# Main.net
KiCad netlist of a schematic drawn in Altium Designer
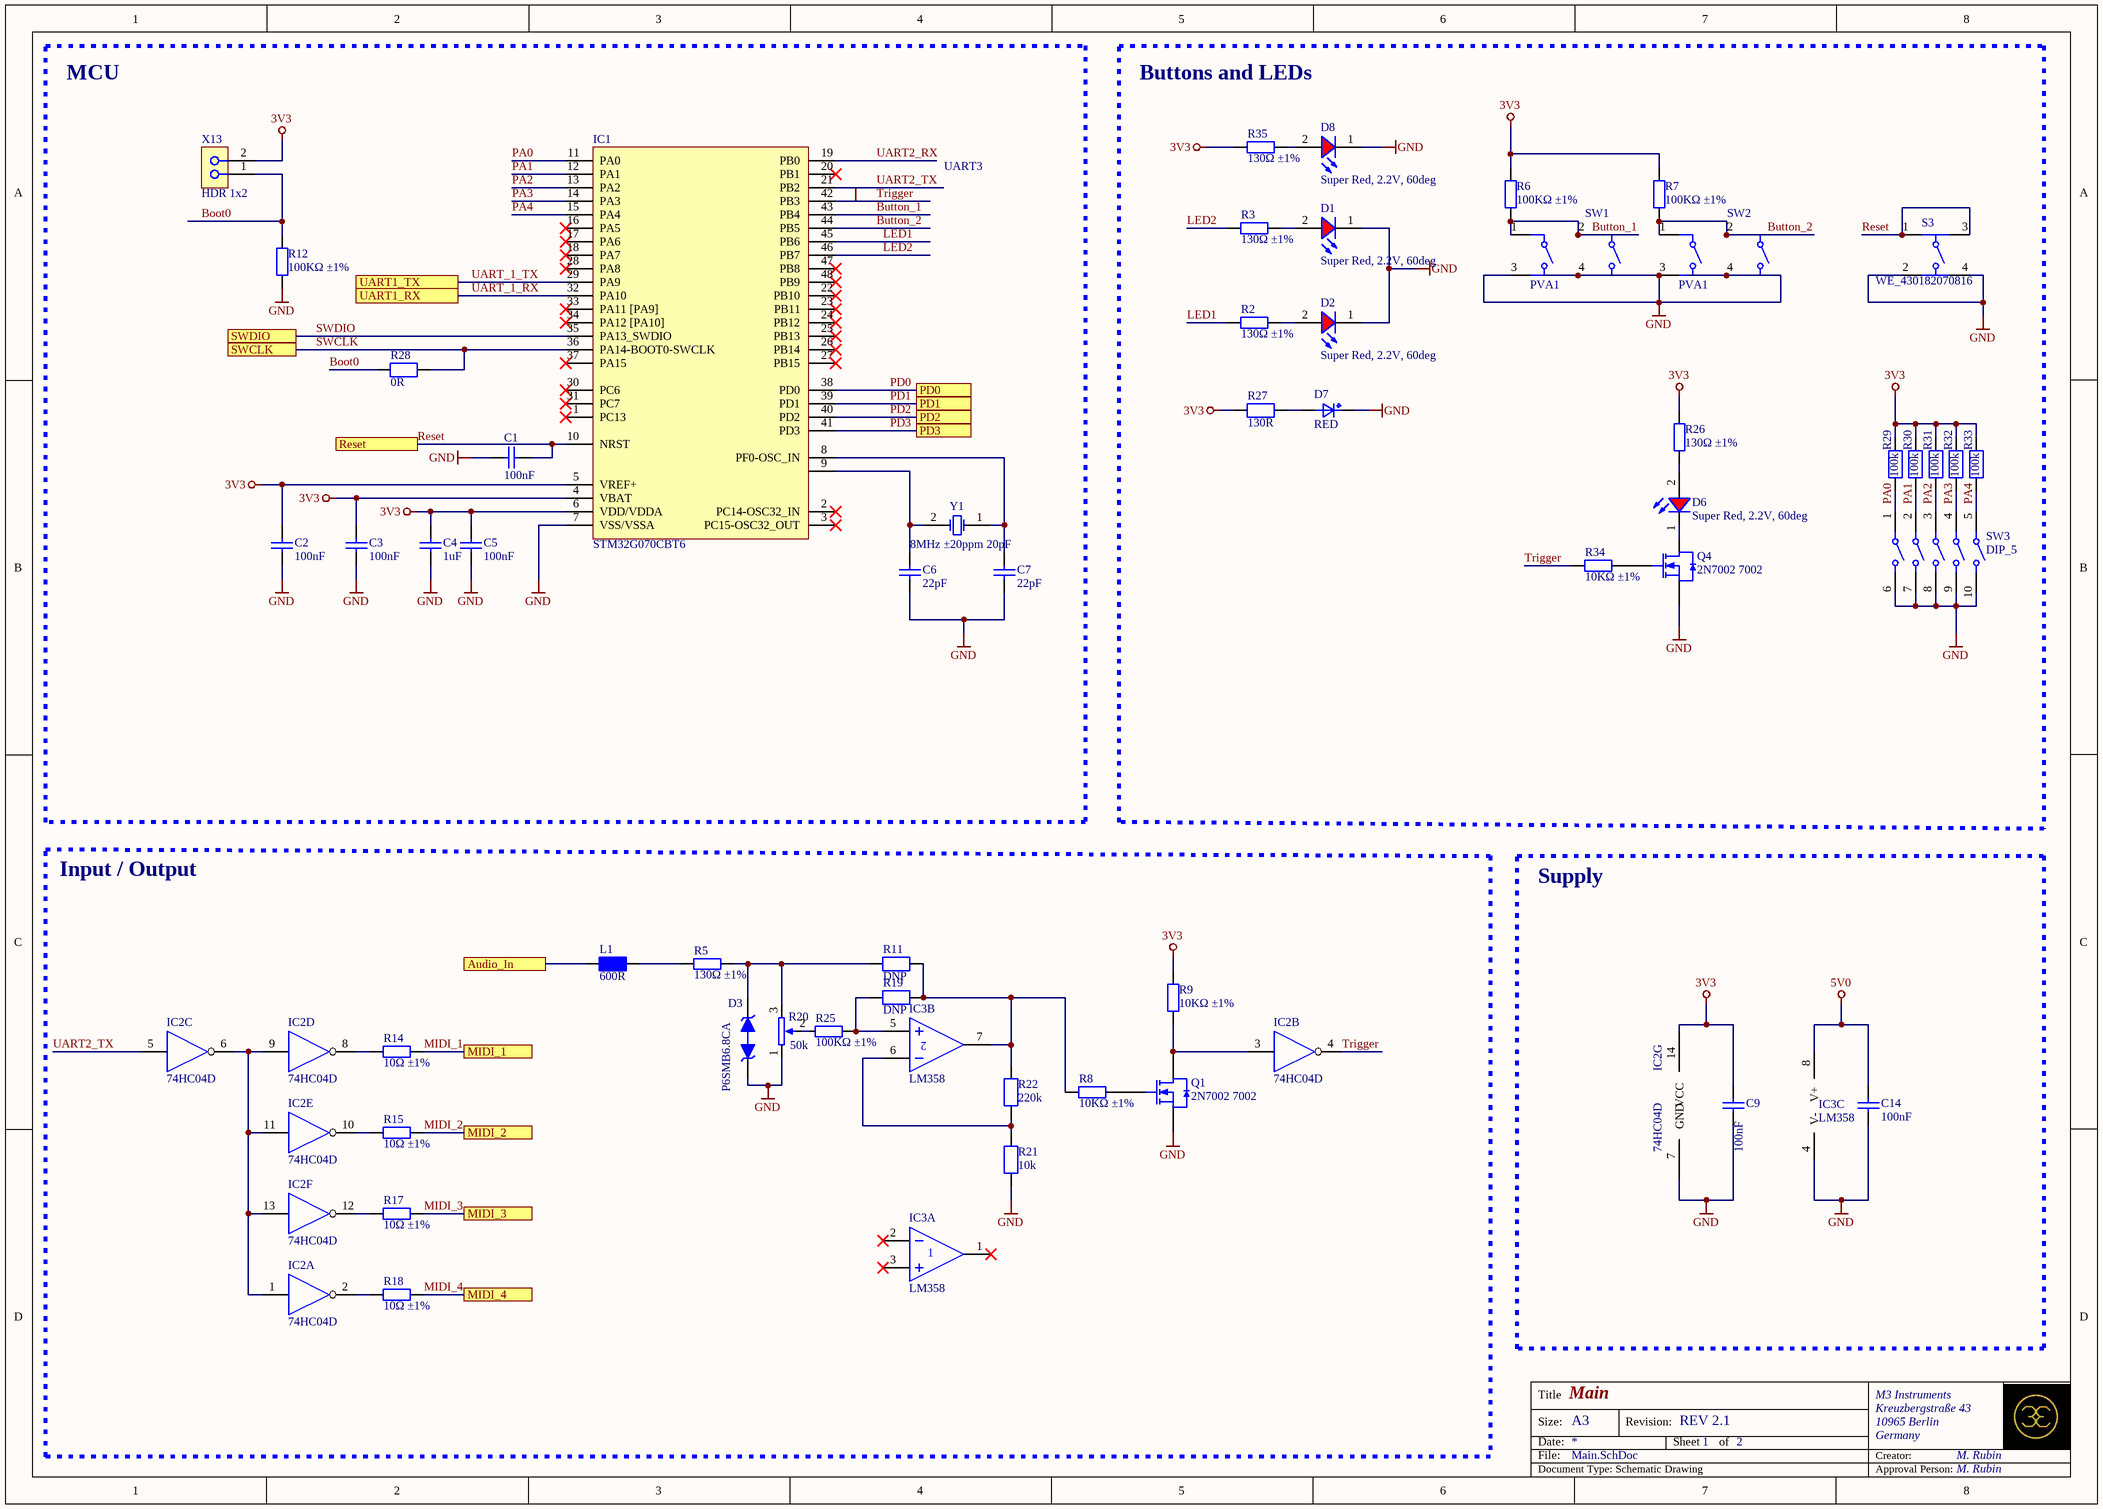
[diagram p0: Main.SchDoc]

(export (version "E")
  (design (tool "Eeschema 10.0.6"))
  (components
    (comp (ref "C1")
      (value "100nF")
      (footprint "CAPC1005X55")
      (description "X7R 100nF ±10% 16V 0402 Multilayer Ceramic Capacitors MLCC - SMD/SMT ROHS")
      (fields
        (field (name "MANUFACTURER") "Samsung Electro-Mechanics")
        (field (name "MANUFACTURER PART NUMBER") "CL05B104KO5NNNC")
      )
      (libsource (lib "Caps") (part "CAP_100nF_0402"))
    )
    (comp (ref "C2")
      (value "100nF")
      (footprint "CAPC1005X55")
      (description "X7R 100nF ±10% 16V 0402 Multilayer Ceramic Capacitors MLCC - SMD/SMT ROHS")
      (fields
        (field (name "MANUFACTURER") "Samsung Electro-Mechanics")
        (field (name "MANUFACTURER PART NUMBER") "CL05B104KO5NNNC")
      )
      (libsource (lib "Caps") (part "CAP_100nF_0402"))
    )
    (comp (ref "C3")
      (value "100nF")
      (footprint "CAPC1005X55")
      (description "X7R 100nF ±10% 16V 0402 Multilayer Ceramic Capacitors MLCC - SMD/SMT ROHS")
      (fields
        (field (name "MANUFACTURER") "Samsung Electro-Mechanics")
        (field (name "MANUFACTURER PART NUMBER") "CL05B104KO5NNNC")
      )
      (libsource (lib "Caps") (part "CAP_100nF_0402"))
    )
    (comp (ref "C4")
      (value "1uF")
      (footprint "CAPC1005X55")
      (description "X5R 25V ±10% 1uF 0402 Multilayer Ceramic Capacitors MLCC - SMD/SMT ROHS")
      (fields
        (field (name "MANUFACTURER") "Samsung Electro-Mechanics")
        (field (name "MANUFACTURER PART NUMBER") "CL05A105KA5NQNC")
      )
      (libsource (lib "Caps") (part "CAP_1uF_0402"))
    )
    (comp (ref "C5")
      (value "100nF")
      (footprint "CAPC1005X55")
      (description "X7R 100nF ±10% 16V 0402 Multilayer Ceramic Capacitors MLCC - SMD/SMT ROHS")
      (fields
        (field (name "MANUFACTURER") "Samsung Electro-Mechanics")
        (field (name "MANUFACTURER PART NUMBER") "CL05B104KO5NNNC")
      )
      (libsource (lib "Caps") (part "CAP_100nF_0402"))
    )
    (comp (ref "C6")
      (value "22pF")
      (footprint "0603_C")
      (description "Chip capacitors")
      (fields
        (field (name "MANUFACTURER") "Samsung Electro-Mechanics")
        (field (name "PARTNUMBER") "CL10C220JB8NNNC")
      )
      (libsource (lib "Cap") (part "0603 22pF (220) 5% 50V"))
    )
    (comp (ref "C7")
      (value "22pF")
      (footprint "0603_C")
      (description "Chip capacitors")
      (fields
        (field (name "MANUFACTURER") "Samsung Electro-Mechanics")
        (field (name "PARTNUMBER") "CL10C220JB8NNNC")
      )
      (libsource (lib "Cap") (part "0603 22pF (220) 5% 50V"))
    )
    (comp (ref "C9")
      (value "100nF")
      (footprint "0603_C")
      (description "Chip capacitors")
      (fields (field (name "MANUFACTURER") "YAGEO") (field (name "PARTNUMBER") "CC0603KRX7R9BB104"))
      (libsource (lib "Cap") (part "0603 100nF (104) 10% 50V"))
    )
    (comp (ref "C14")
      (value "100nF")
      (footprint "0603_C")
      (description "Chip capacitors")
      (fields (field (name "MANUFACTURER") "YAGEO") (field (name "PARTNUMBER") "CC0603KRX7R9BB104"))
      (libsource (lib "Cap") (part "0603 100nF (104) 10% 50V"))
    )
    (comp (ref "D1")
      (value "Super Red, 2.2V, 60deg")
      (footprint "WL-TMRC_3mm_17mm_space")
      (description "WL-TMRC THT Mono-color Round Color, size 3mm, Super Red, 2.2V, 60deg")
      (fields (field (name "PART NUMBER") "151031SS06000") (field (name "PUBLISHER") "Wurth Elektronik"))
      (libsource (lib "Diodes") (part "151031SS06000_Spacer"))
    )
    (comp (ref "D2")
      (value "Super Red, 2.2V, 60deg")
      (footprint "WL-TMRC_3mm_17mm_space")
      (description "WL-TMRC THT Mono-color Round Color, size 3mm, Super Red, 2.2V, 60deg")
      (fields (field (name "PART NUMBER") "151031SS06000") (field (name "PUBLISHER") "Wurth Elektronik"))
      (libsource (lib "Diodes") (part "151031SS06000_Spacer"))
    )
    (comp (ref "D3")
      (value "P6SMB6.8CA")
      (footprint "SMB(DO-214AA)_S1")
      (description "TVS 6.8V")
      (fields (field (name "MANUFACTURER") "Brightking Elec"))
      (libsource (lib "Diodes") (part "DIO_P6SMB6.8CA"))
    )
    (comp (ref "D6")
      (value "Super Red, 2.2V, 60deg")
      (footprint "WL-TMRC_3mm_17mm_space")
      (description "WL-TMRC THT Mono-color Round Color, size 3mm, Super Red, 2.2V, 60deg")
      (fields (field (name "PART NUMBER") "151031SS06000") (field (name "PUBLISHER") "Wurth Elektronik"))
      (libsource (lib "Diodes") (part "151031SS06000_Spacer"))
    )
    (comp (ref "D7")
      (value "RED")
      (footprint "WL-SMCW_0805")
      (description "Standard LEDs - SMD WL-SMCW SMDMono TpVw Waterclr 0805 Red")
      (fields
        (field (name "MANUFACTURER") "Wurth Elektronik")
        (field (name "MANUFACTURER PART NUMBER") "150080RS75000")
      )
      (libsource (lib "Diodes") (part "LED_0805_RED_AK"))
    )
    (comp (ref "D8")
      (value "Super Red, 2.2V, 60deg")
      (footprint "WL-TMRC_3mm_17mm_space")
      (description "WL-TMRC THT Mono-color Round Color, size 3mm, Super Red, 2.2V, 60deg")
      (fields (field (name "PART NUMBER") "151031SS06000") (field (name "PUBLISHER") "Wurth Elektronik"))
      (libsource (lib "Diodes") (part "151031SS06000_Spacer"))
    )
    (comp (ref "IC1")
      (value "STM32G070CBT6")
      (footprint "LQFP-48_7x7x05P")
      (fields (field (name "MANUFACTURER") "STMicroelectronics"))
      (libsource (lib "ICs") (part "STM32G070CBT6"))
    )
    (comp (ref "IC2")
      (value "74HC04D")
      (footprint "SOIC-14_150mil")
      (description "74系列逻辑芯片")
      (libsource (lib "IC") (part "74HC04D_[C5590]"))
    )
    (comp (ref "IC3")
      (value "LM358")
      (footprint "SOIC127P600X175-8N")
      (fields
        (field (name "MANUFACTURER") "ON Semiconductor")
        (field (name "MANUFACTURER PART NUMBER") "LM358DR2G")
      )
      (libsource (lib "ICs") (part "IC_LM358DR2G"))
    )
    (comp (ref "L1")
      (value "600R")
      (footprint "INDC2012X85N")
      (description "Ferrite Beads 0805 600 OHM")
      (fields
        (field (name "MANUFACTURER") "Murata Electronics")
        (field (name "MANUFACTURER PART NUMBER") "BLM21AG601SN1D")
      )
      (libsource (lib "Inductors") (part "FB_600R_600mA_0805"))
    )
    (comp (ref "Q1")
      (value "2N7002 7002")
      (footprint "SOT-23(SOT-23-3)")
      (description "MOS(场效应管)")
      (libsource (lib "MOS") (part "2N7002 7002"))
    )
    (comp (ref "Q4")
      (value "2N7002 7002")
      (footprint "SOT-23(SOT-23-3)")
      (description "MOS(场效应管)")
      (libsource (lib "MOS") (part "2N7002 7002"))
    )
    (comp (ref "R2")
      (value "130Ω ±1%")
      (footprint "0603_R")
      (description "Chip resistor")
      (fields (field (name "MANUFACTURER") "Uniroyal Elec") (field (name "PARTNUMBER") "0603WAF1300T5E"))
      (libsource (lib "RES") (part "0603 130R (1300) 1%"))
    )
    (comp (ref "R3")
      (value "130Ω ±1%")
      (footprint "0603_R")
      (description "Chip resistor")
      (fields (field (name "MANUFACTURER") "Uniroyal Elec") (field (name "PARTNUMBER") "0603WAF1300T5E"))
      (libsource (lib "RES") (part "0603 130R (1300) 1%"))
    )
    (comp (ref "R5")
      (value "130Ω ±1%")
      (footprint "0603_R")
      (description "Chip resistor")
      (fields (field (name "MANUFACTURER") "Uniroyal Elec") (field (name "PARTNUMBER") "0603WAF1300T5E"))
      (libsource (lib "RES") (part "0603 130R (1300) 1%"))
    )
    (comp (ref "R6")
      (value "100KΩ ±1%")
      (footprint "0603_R")
      (description "Chip resistor")
      (fields (field (name "MANUFACTURER") "Uniroyal Elec") (field (name "PARTNUMBER") "0603WAF1003T5E"))
      (libsource (lib "RES") (part "0603 100K (1003) 1%"))
    )
    (comp (ref "R7")
      (value "100KΩ ±1%")
      (footprint "0603_R")
      (description "Chip resistor")
      (fields (field (name "MANUFACTURER") "Uniroyal Elec") (field (name "PARTNUMBER") "0603WAF1003T5E"))
      (libsource (lib "RES") (part "0603 100K (1003) 1%"))
    )
    (comp (ref "R8")
      (value "10KΩ ±1%")
      (footprint "0603_R")
      (description "Chip resistor")
      (fields (field (name "MANUFACTURER") "Uniroyal Elec") (field (name "PARTNUMBER") "0603WAF1002T5E"))
      (libsource (lib "") (part "0603 10K (1002) 1%_1"))
    )
    (comp (ref "R9")
      (value "10KΩ ±1%")
      (footprint "0603_R")
      (description "Chip resistor")
      (fields (field (name "MANUFACTURER") "Uniroyal Elec") (field (name "PARTNUMBER") "0603WAF1002T5E"))
      (libsource (lib "RES") (part "0603 10K (1002) 1%"))
    )
    (comp (ref "R11")
      (value "DNP")
      (footprint "RESC1608X55N")
      (description "Resistor SMD 0603 - not populated")
      (libsource (lib "Resistors") (part "RES_DNF_0603"))
    )
    (comp (ref "R12")
      (value "100KΩ ±1%")
      (footprint "0603_R")
      (description "Chip resistor")
      (fields (field (name "MANUFACTURER") "Uniroyal Elec") (field (name "PARTNUMBER") "0603WAF1003T5E"))
      (libsource (lib "RES") (part "0603 100K (1003) 1%"))
    )
    (comp (ref "R14")
      (value "10Ω ±1%")
      (footprint "0603_R")
      (description "Chip resistor")
      (fields (field (name "MANUFACTURER") "Uniroyal Elec") (field (name "PARTNUMBER") "0603WAF100JT5E"))
      (libsource (lib "RES") (part "0603 10R (10R0) 1%"))
    )
    (comp (ref "R15")
      (value "10Ω ±1%")
      (footprint "0603_R")
      (description "Chip resistor")
      (fields (field (name "MANUFACTURER") "Uniroyal Elec") (field (name "PARTNUMBER") "0603WAF100JT5E"))
      (libsource (lib "RES") (part "0603 10R (10R0) 1%"))
    )
    (comp (ref "R17")
      (value "10Ω ±1%")
      (footprint "0603_R")
      (description "Chip resistor")
      (fields (field (name "MANUFACTURER") "Uniroyal Elec") (field (name "PARTNUMBER") "0603WAF100JT5E"))
      (libsource (lib "RES") (part "0603 10R (10R0) 1%"))
    )
    (comp (ref "R18")
      (value "10Ω ±1%")
      (footprint "0603_R")
      (description "Chip resistor")
      (fields (field (name "MANUFACTURER") "Uniroyal Elec") (field (name "PARTNUMBER") "0603WAF100JT5E"))
      (libsource (lib "RES") (part "0603 10R (10R0) 1%"))
    )
    (comp (ref "R19")
      (value "DNP")
      (footprint "RESC1608X55N")
      (description "Resistor SMD 0603 - not populated")
      (libsource (lib "Resistors") (part "RES_DNF_0603"))
    )
    (comp (ref "R20")
      (value "50k")
      (footprint "RK09K111")
      (description "Potentiometers 10K HOIRZONTAL")
      (fields
        (field (name "MANUFACTURER") "Alps Alpine")
        (field (name "MANUFACTURER PART NUMBER") "RK09K111-LIN10K")
      )
      (libsource (lib "Resistors") (part "POT_50k_lin_small"))
    )
    (comp (ref "R21")
      (value "10k")
      (footprint "RESC2012X70N")
      (description "Thick Film Resistors - SMD 1/8watt 10Kohms 1% 100ppm")
      (fields
        (field (name "MANUFACTURER") "Vishay / Dale")
        (field (name "MANUFACTURER PART NUMBER") "CRCW080510K0FKEA")
      )
      (libsource (lib "Resistors") (part "RES_10k_0805"))
    )
    (comp (ref "R22")
      (value "220k")
      (footprint "RESC2012X70N")
      (description "Thick Film Resistors - SMD 1/8watt 220Kohms 1%")
      (fields
        (field (name "MANUFACTURER") "Vishay / Dale")
        (field (name "MANUFACTURER PART NUMBER") "CRCW0805220KFKEA")
      )
      (libsource (lib "Resistors") (part "RES_220k_0805"))
    )
    (comp (ref "R25")
      (value "100KΩ ±1%")
      (footprint "0603_R")
      (description "Chip resistor")
      (fields (field (name "MANUFACTURER") "Uniroyal Elec") (field (name "PARTNUMBER") "0603WAF1003T5E"))
      (libsource (lib "") (part "0603 100K (1003) 1%_1"))
    )
    (comp (ref "R26")
      (value "130Ω ±1%")
      (footprint "0603_R")
      (description "Chip resistor")
      (fields (field (name "MANUFACTURER") "Uniroyal Elec") (field (name "PARTNUMBER") "0603WAF1300T5E"))
      (libsource (lib "") (part "0603 130R (1300) 1%_1"))
    )
    (comp (ref "R27")
      (value "130R")
      (footprint "RESC2012X70N")
      (description "Dickfilmwiderstände - SMD 1/8watt 130ohms 1% 100ppm")
      (fields
        (field (name "MANUFACTURER") "Vishay / Dale")
        (field (name "MANUFACTURER PART NUMBER") "CRCW0805130RFKEA")
      )
      (libsource (lib "Resistors") (part "RES_130R_0805"))
    )
    (comp (ref "R28")
      (value "0R")
      (footprint "RESC2012X70N")
      (description "Thick Film Resistors - SMD 1/8watt ZEROohm Jumper")
      (fields
        (field (name "MANUFACTURER") "Vishay")
        (field (name "MANUFACTURER PART NUMBER") "CRCW08050000Z0EA")
      )
      (libsource (lib "Resistors") (part "RES_0R_0805"))
    )
    (comp (ref "R29")
      (value "100k")
      (footprint "RESC2012X70N")
      (description "Thick Film Resistors - SMD 1/8watt 100Kohms 1% 100ppm")
      (fields (field (name "MANUFACTURER") "Vishay / Dale") (field (name "TOLERANCE") "1%"))
      (libsource (lib "Resistors") (part "RES_100k_0805"))
    )
    (comp (ref "R30")
      (value "100k")
      (footprint "RESC2012X70N")
      (description "Thick Film Resistors - SMD 1/8watt 100Kohms 1% 100ppm")
      (fields (field (name "MANUFACTURER") "Vishay / Dale") (field (name "TOLERANCE") "1%"))
      (libsource (lib "Resistors") (part "RES_100k_0805"))
    )
    (comp (ref "R31")
      (value "100k")
      (footprint "RESC2012X70N")
      (description "Thick Film Resistors - SMD 1/8watt 100Kohms 1% 100ppm")
      (fields (field (name "MANUFACTURER") "Vishay / Dale") (field (name "TOLERANCE") "1%"))
      (libsource (lib "Resistors") (part "RES_100k_0805"))
    )
    (comp (ref "R32")
      (value "100k")
      (footprint "RESC2012X70N")
      (description "Thick Film Resistors - SMD 1/8watt 100Kohms 1% 100ppm")
      (fields (field (name "MANUFACTURER") "Vishay / Dale") (field (name "TOLERANCE") "1%"))
      (libsource (lib "Resistors") (part "RES_100k_0805"))
    )
    (comp (ref "R33")
      (value "100k")
      (footprint "RESC2012X70N")
      (description "Thick Film Resistors - SMD 1/8watt 100Kohms 1% 100ppm")
      (fields (field (name "MANUFACTURER") "Vishay / Dale") (field (name "TOLERANCE") "1%"))
      (libsource (lib "Resistors") (part "RES_100k_0805"))
    )
    (comp (ref "R34")
      (value "10KΩ ±1%")
      (footprint "0603_R")
      (description "Chip resistor")
      (fields (field (name "MANUFACTURER") "Uniroyal Elec") (field (name "PARTNUMBER") "0603WAF1002T5E"))
      (libsource (lib "") (part "0603 10K (1002) 1%_1"))
    )
    (comp (ref "R35")
      (value "130Ω ±1%")
      (footprint "0603_R")
      (description "Chip resistor")
      (fields (field (name "MANUFACTURER") "Uniroyal Elec") (field (name "PARTNUMBER") "0603WAF1300T5E"))
      (libsource (lib "RES") (part "0603 130R (1300) 1%"))
    )
    (comp (ref "S3")
      (value "WE_430182070816")
      (footprint "430182070816")
      (description "WS-TASV SMT Tact Switch 6x6mm, height 7mm, 160gf")
      (fields (field (name "PART NUMBER") "430182070816") (field (name "PUBLISHER") "Wurth Elektronik"))
      (libsource (lib "Switches") (part "WE_430182070816"))
    )
    (comp (ref "SW1")
      (value "PVA1")
      (footprint "C&K_PVA1")
      (description "Druckschalter DPST-Schließer Tastenschalter Durchkontaktierung")
      (fields
        (field (name "MANUFACTURER") "C&K")
        (field (name "MANUFACTURER PART NUMBER") "PVA1 OA H3 1.2N V2")
      )
      (libsource (lib "Switches") (part "C&K_PVA1_OA_H3_1.2N_V2"))
    )
    (comp (ref "SW2")
      (value "PVA1")
      (footprint "C&K_PVA1")
      (description "Druckschalter DPST-Schließer Tastenschalter Durchkontaktierung")
      (fields
        (field (name "MANUFACTURER") "C&K")
        (field (name "MANUFACTURER PART NUMBER") "PVA1 OA H3 1.2N V2")
      )
      (libsource (lib "Switches") (part "C&K_PVA1_OA_H3_1.2N_V2"))
    )
    (comp (ref "SW3")
      (value "DIP_5")
      (footprint "HAD-05HWAG-2")
      (description "SPST Black 平拨，凸起式 2.54mm 5 SMD DIP Switches ROHS")
      (fields
        (field (name "MANUFACTURER") "Cixi Tonver Elec")
        (field (name "MANUFACTURER PART NUMBER") "HAD-05HWAG-2")
      )
      (libsource (lib "Switches") (part "DIP_HAD-05HWAG-2"))
    )
    (comp (ref "X13")
      (value "HDR 1x2")
      (footprint "CON_HEADER2.54_1x2W")
      (description "Board-to-Board-Steckverbinder, 2.54 mm, 2 Kontakt(e), Stiftleiste 1-Reihig")
      (fields
        (field (name "MANUFACTURER") "Samtec")
        (field (name "MANUFACTURER PART NUMBER") "TSW-102-07-T-S")
      )
      (libsource (lib "Connectors") (part "CON_HEADER_1X2"))
    )
    (comp (ref "Y1")
      (value "8MHz ±20ppm 20pF")
      (footprint "SMD-5032_2P")
      (description "贴片晶振")
      (libsource (lib "CrystalOscillator") (part "SMD-5032_2P 8MHz 20ppm 20pF"))
    )
  )
  (nets
    (net (code "1") (name "/Audio_In") (class "Default")
      (node (ref "L1") (pin "1") (pinfunction "1_1") (pintype "passive"))
    )
    (net (code "2") (name "/Boot0") (class "Default")
      (node (ref "R12") (pin "2") (pinfunction "2_2") (pintype "passive"))
      (node (ref "R28") (pin "1") (pinfunction "1_1") (pintype "passive"))
      (node (ref "X13") (pin "1") (pinfunction "1_1") (pintype "passive"))
    )
    (net (code "3") (name "/Button_1") (class "Default")
      (node (ref "IC1") (pin "43") (pinfunction "PB4_43") (pintype "passive"))
      (node (ref "R6") (pin "1") (pinfunction "1_1") (pintype "passive"))
      (node (ref "SW1") (pin "1") (pinfunction "1_1") (pintype "passive"))
      (node (ref "SW1") (pin "2") (pinfunction "2_2") (pintype "passive"))
    )
    (net (code "4") (name "/Button_2") (class "Default")
      (node (ref "IC1") (pin "44") (pinfunction "PB5_44") (pintype "passive"))
      (node (ref "R7") (pin "1") (pinfunction "1_1") (pintype "passive"))
      (node (ref "SW2") (pin "1") (pinfunction "1_1") (pintype "passive"))
      (node (ref "SW2") (pin "2") (pinfunction "2_2") (pintype "passive"))
    )
    (net (code "5") (name "/LED1") (class "Default")
      (node (ref "IC1") (pin "45") (pinfunction "PB6_45") (pintype "passive"))
      (node (ref "R2") (pin "2") (pinfunction "2_2") (pintype "passive"))
    )
    (net (code "6") (name "/LED2") (class "Default")
      (node (ref "IC1") (pin "46") (pinfunction "PB7_46") (pintype "passive"))
      (node (ref "R3") (pin "2") (pinfunction "2_2") (pintype "passive"))
    )
    (net (code "7") (name "/MIDI_1") (class "Default")
      (node (ref "R14") (pin "2") (pinfunction "2_2") (pintype "passive"))
    )
    (net (code "8") (name "/MIDI_2") (class "Default")
      (node (ref "R15") (pin "2") (pinfunction "2_2") (pintype "passive"))
    )
    (net (code "9") (name "/MIDI_3") (class "Default")
      (node (ref "R17") (pin "2") (pinfunction "2_2") (pintype "passive"))
    )
    (net (code "10") (name "/MIDI_4") (class "Default")
      (node (ref "R18") (pin "2") (pinfunction "2_2") (pintype "passive"))
    )
    (net (code "11") (name "/PA0") (class "Default")
      (node (ref "IC1") (pin "11") (pinfunction "PA0_11") (pintype "passive"))
      (node (ref "R29") (pin "1") (pinfunction "1_1") (pintype "passive"))
      (node (ref "SW3") (pin "1") (pinfunction "1_1") (pintype "passive"))
    )
    (net (code "12") (name "/PA1") (class "Default")
      (node (ref "IC1") (pin "12") (pinfunction "PA1_12") (pintype "passive"))
      (node (ref "R30") (pin "1") (pinfunction "1_1") (pintype "passive"))
      (node (ref "SW3") (pin "2") (pinfunction "2_2") (pintype "passive"))
    )
    (net (code "13") (name "/PA2") (class "Default")
      (node (ref "IC1") (pin "13") (pinfunction "PA2_13") (pintype "passive"))
      (node (ref "R31") (pin "1") (pinfunction "1_1") (pintype "passive"))
      (node (ref "SW3") (pin "3") (pinfunction "3_3") (pintype "passive"))
    )
    (net (code "14") (name "/PA3") (class "Default")
      (node (ref "IC1") (pin "14") (pinfunction "PA3_14") (pintype "passive"))
      (node (ref "R32") (pin "1") (pinfunction "1_1") (pintype "passive"))
      (node (ref "SW3") (pin "4") (pinfunction "4_4") (pintype "passive"))
    )
    (net (code "15") (name "/PA4") (class "Default")
      (node (ref "IC1") (pin "15") (pinfunction "PA4_15") (pintype "passive"))
      (node (ref "R33") (pin "1") (pinfunction "1_1") (pintype "passive"))
      (node (ref "SW3") (pin "5") (pinfunction "5_5") (pintype "passive"))
    )
    (net (code "16") (name "/PD0") (class "Default")
      (node (ref "IC1") (pin "38") (pinfunction "PD0_38") (pintype "passive"))
    )
    (net (code "17") (name "/PD1") (class "Default")
      (node (ref "IC1") (pin "39") (pinfunction "PD1_39") (pintype "passive"))
    )
    (net (code "18") (name "/PD2") (class "Default")
      (node (ref "IC1") (pin "40") (pinfunction "PD2_40") (pintype "passive"))
    )
    (net (code "19") (name "/PD3") (class "Default")
      (node (ref "IC1") (pin "41") (pinfunction "PD3_41") (pintype "passive"))
    )
    (net (code "20") (name "/Reset") (class "Default")
      (node (ref "C1") (pin "1") (pinfunction "1_1") (pintype "passive"))
      (node (ref "IC1") (pin "10") (pinfunction "NRST_10") (pintype "passive"))
      (node (ref "S3") (pin "1") (pinfunction "1_1") (pintype "passive"))
      (node (ref "S3") (pin "3") (pinfunction "3_3") (pintype "passive"))
    )
    (net (code "21") (name "/SWCLK") (class "Default")
      (node (ref "IC1") (pin "36") (pinfunction "PA14-BOOT0-SWCLK_36") (pintype "power_in"))
      (node (ref "R28") (pin "2") (pinfunction "2_2") (pintype "passive"))
    )
    (net (code "22") (name "/SWDIO") (class "Default")
      (node (ref "IC1") (pin "35") (pinfunction "PA13_SWDIO_35") (pintype "power_in"))
    )
    (net (code "23") (name "/Trigger") (class "Default")
      (node (ref "IC1") (pin "42") (pinfunction "PB3_42") (pintype "passive"))
      (node (ref "IC2") (pin "4") (pinfunction "Y_4") (pintype "passive"))
      (node (ref "R34") (pin "1") (pinfunction "1_1") (pintype "passive"))
    )
    (net (code "24") (name "/UART2_RX") (class "Default")
      (node (ref "IC1") (pin "19") (pinfunction "PB0_19") (pintype "passive"))
    )
    (net (code "25") (name "/UART2_TX") (class "Default")
      (node (ref "IC1") (pin "21") (pinfunction "PB2_21") (pintype "passive"))
      (node (ref "IC2") (pin "5") (pinfunction "A_5") (pintype "passive"))
    )
    (net (code "26") (name "/UART_1_RX") (class "Default")
      (node (ref "IC1") (pin "32") (pinfunction "PA10_32") (pintype "passive"))
    )
    (net (code "27") (name "/UART_1_TX") (class "Default")
      (node (ref "IC1") (pin "29") (pinfunction "PA9_29") (pintype "passive"))
    )
    (net (code "28") (name "3V3") (class "Default")
      (node (ref "C2") (pin "2") (pinfunction "2_2") (pintype "passive"))
      (node (ref "C3") (pin "2") (pinfunction "2_2") (pintype "passive"))
      (node (ref "C4") (pin "2") (pinfunction "2_2") (pintype "passive"))
      (node (ref "C5") (pin "2") (pinfunction "2_2") (pintype "passive"))
      (node (ref "C9") (pin "2") (pinfunction "2_2") (pintype "passive"))
      (node (ref "IC1") (pin "4") (pinfunction "VBAT_4") (pintype "passive"))
      (node (ref "IC1") (pin "5") (pinfunction "VREF+_5") (pintype "passive"))
      (node (ref "IC1") (pin "6") (pinfunction "VDD/VDDA_6") (pintype "passive"))
      (node (ref "IC2") (pin "14") (pinfunction "VCC_14") (pintype "passive"))
      (node (ref "R26") (pin "2") (pinfunction "2_2") (pintype "passive"))
      (node (ref "R27") (pin "1") (pinfunction "1_1") (pintype "passive"))
      (node (ref "R29") (pin "2") (pinfunction "2_2") (pintype "passive"))
      (node (ref "R30") (pin "2") (pinfunction "2_2") (pintype "passive"))
      (node (ref "R31") (pin "2") (pinfunction "2_2") (pintype "passive"))
      (node (ref "R32") (pin "2") (pinfunction "2_2") (pintype "passive"))
      (node (ref "R33") (pin "2") (pinfunction "2_2") (pintype "passive"))
      (node (ref "R35") (pin "2") (pinfunction "2_2") (pintype "passive"))
      (node (ref "R6") (pin "2") (pinfunction "2_2") (pintype "passive"))
      (node (ref "R7") (pin "2") (pinfunction "2_2") (pintype "passive"))
      (node (ref "R9") (pin "2") (pinfunction "2_2") (pintype "passive"))
      (node (ref "X13") (pin "2") (pinfunction "2_2") (pintype "passive"))
    )
    (net (code "29") (name "5V0") (class "Default")
      (node (ref "C14") (pin "2") (pinfunction "2_2") (pintype "passive"))
      (node (ref "IC3") (pin "8") (pinfunction "V+_8") (pintype "power_in"))
    )
    (net (code "30") (name "GND") (class "Default")
      (node (ref "C1") (pin "2") (pinfunction "2_2") (pintype "passive"))
      (node (ref "C14") (pin "1") (pinfunction "1_1") (pintype "passive"))
      (node (ref "C2") (pin "1") (pinfunction "1_1") (pintype "passive"))
      (node (ref "C3") (pin "1") (pinfunction "1_1") (pintype "passive"))
      (node (ref "C4") (pin "1") (pinfunction "1_1") (pintype "passive"))
      (node (ref "C5") (pin "1") (pinfunction "1_1") (pintype "passive"))
      (node (ref "C6") (pin "2") (pinfunction "2_2") (pintype "passive"))
      (node (ref "C7") (pin "2") (pinfunction "2_2") (pintype "passive"))
      (node (ref "C9") (pin "1") (pinfunction "1_1") (pintype "passive"))
      (node (ref "D1") (pin "1") (pinfunction "K_1") (pintype "passive"))
      (node (ref "D2") (pin "1") (pinfunction "K_1") (pintype "passive"))
      (node (ref "D3") (pin "A1") (pinfunction "A1_A1") (pintype "passive"))
      (node (ref "D7") (pin "K") (pinfunction "K_K") (pintype "passive"))
      (node (ref "D8") (pin "1") (pinfunction "K_1") (pintype "passive"))
      (node (ref "IC1") (pin "7") (pinfunction "VSS/VSSA_7") (pintype "passive"))
      (node (ref "IC2") (pin "7") (pinfunction "GND_7") (pintype "passive"))
      (node (ref "IC3") (pin "4") (pinfunction "V-_4") (pintype "power_in"))
      (node (ref "Q1") (pin "2") (pinfunction "S_2") (pintype "passive"))
      (node (ref "Q4") (pin "2") (pinfunction "S_2") (pintype "passive"))
      (node (ref "R12") (pin "1") (pinfunction "1_1") (pintype "passive"))
      (node (ref "R20") (pin "1") (pinfunction "1_1") (pintype "passive"))
      (node (ref "R21") (pin "1") (pinfunction "1_1") (pintype "passive"))
      (node (ref "S3") (pin "2") (pinfunction "2_2") (pintype "passive"))
      (node (ref "S3") (pin "4") (pinfunction "4_4") (pintype "passive"))
      (node (ref "SW1") (pin "3") (pinfunction "3_3") (pintype "passive"))
      (node (ref "SW1") (pin "4") (pinfunction "4_4") (pintype "passive"))
      (node (ref "SW2") (pin "3") (pinfunction "3_3") (pintype "passive"))
      (node (ref "SW2") (pin "4") (pinfunction "4_4") (pintype "passive"))
      (node (ref "SW3") (pin "10") (pinfunction "10_10") (pintype "passive"))
      (node (ref "SW3") (pin "6") (pinfunction "6_6") (pintype "passive"))
      (node (ref "SW3") (pin "7") (pinfunction "7_7") (pintype "passive"))
      (node (ref "SW3") (pin "8") (pinfunction "8_8") (pintype "passive"))
      (node (ref "SW3") (pin "9") (pinfunction "9_9") (pintype "passive"))
    )
    (net (code "31") (name "Net-(D1-A)") (class "Default")
      (node (ref "D1") (pin "2") (pinfunction "A_2") (pintype "passive"))
      (node (ref "R3") (pin "1") (pinfunction "1_1") (pintype "passive"))
    )
    (net (code "32") (name "Net-(D2-A)") (class "Default")
      (node (ref "D2") (pin "2") (pinfunction "A_2") (pintype "passive"))
      (node (ref "R2") (pin "1") (pinfunction "1_1") (pintype "passive"))
    )
    (net (code "33") (name "Net-(D3-PadA2)") (class "Default")
      (node (ref "D3") (pin "A2") (pinfunction "A2_A2") (pintype "passive"))
      (node (ref "R11") (pin "2") (pinfunction "2_2") (pintype "passive"))
      (node (ref "R20") (pin "3") (pinfunction "3_3") (pintype "passive"))
      (node (ref "R5") (pin "1") (pinfunction "1_1") (pintype "passive"))
    )
    (net (code "34") (name "Net-(D6-A)") (class "Default")
      (node (ref "D6") (pin "2") (pinfunction "A_2") (pintype "passive"))
      (node (ref "R26") (pin "1") (pinfunction "1_1") (pintype "passive"))
    )
    (net (code "35") (name "Net-(D6-K)") (class "Default")
      (node (ref "D6") (pin "1") (pinfunction "K_1") (pintype "passive"))
      (node (ref "Q4") (pin "3") (pinfunction "D_3") (pintype "passive"))
    )
    (net (code "36") (name "Net-(D7-PadA)") (class "Default")
      (node (ref "D7") (pin "A") (pinfunction "A_A") (pintype "passive"))
      (node (ref "R27") (pin "2") (pinfunction "2_2") (pintype "passive"))
    )
    (net (code "37") (name "Net-(D8-A)") (class "Default")
      (node (ref "D8") (pin "2") (pinfunction "A_2") (pintype "passive"))
      (node (ref "R35") (pin "1") (pinfunction "1_1") (pintype "passive"))
    )
    (net (code "38") (name "Net-(IC1-PF0-OSC_IN)") (class "Default")
      (node (ref "C7") (pin "1") (pinfunction "1_1") (pintype "passive"))
      (node (ref "IC1") (pin "8") (pinfunction "PF0-OSC_IN_8") (pintype "power_in"))
      (node (ref "Y1") (pin "1") (pinfunction "OSC1_1") (pintype "passive"))
    )
    (net (code "39") (name "Net-(IC1-PF1-OSC_OU'T)") (class "Default")
      (node (ref "C6") (pin "1") (pinfunction "1_1") (pintype "passive"))
      (node (ref "IC1") (pin "9") (pinfunction "PF1-OSC_OU'T_9") (pintype "power_in"))
      (node (ref "Y1") (pin "2") (pinfunction "OSC2_2") (pintype "passive"))
    )
    (net (code "40") (name "Net-(IC2A-A)") (class "Default")
      (node (ref "IC2") (pin "1") (pinfunction "A_1") (pintype "passive"))
      (node (ref "IC2") (pin "11") (pinfunction "A_11") (pintype "passive"))
      (node (ref "IC2") (pin "13") (pinfunction "A_13") (pintype "passive"))
      (node (ref "IC2") (pin "6") (pinfunction "Y_6") (pintype "passive"))
      (node (ref "IC2") (pin "9") (pinfunction "A_9") (pintype "passive"))
    )
    (net (code "41") (name "Net-(IC2A-Y)") (class "Default")
      (node (ref "IC2") (pin "2") (pinfunction "Y_2") (pintype "passive"))
      (node (ref "R18") (pin "1") (pinfunction "1_1") (pintype "passive"))
    )
    (net (code "42") (name "Net-(IC2B-A)") (class "Default")
      (node (ref "IC2") (pin "3") (pinfunction "A_3") (pintype "passive"))
      (node (ref "Q1") (pin "3") (pinfunction "D_3") (pintype "passive"))
      (node (ref "R9") (pin "1") (pinfunction "1_1") (pintype "passive"))
    )
    (net (code "43") (name "Net-(IC2D-Y)") (class "Default")
      (node (ref "IC2") (pin "8") (pinfunction "Y_8") (pintype "passive"))
      (node (ref "R14") (pin "1") (pinfunction "1_1") (pintype "passive"))
    )
    (net (code "44") (name "Net-(IC2E-Y)") (class "Default")
      (node (ref "IC2") (pin "10") (pinfunction "Y_10") (pintype "passive"))
      (node (ref "R15") (pin "1") (pinfunction "1_1") (pintype "passive"))
    )
    (net (code "45") (name "Net-(IC2F-Y)") (class "Default")
      (node (ref "IC2") (pin "12") (pinfunction "Y_12") (pintype "passive"))
      (node (ref "R17") (pin "1") (pinfunction "1_1") (pintype "passive"))
    )
    (net (code "46") (name "Net-(IC3B-IN+)") (class "Default")
      (node (ref "IC3") (pin "5") (pinfunction "IN+_5") (pintype "passive"))
      (node (ref "R19") (pin "2") (pinfunction "2_2") (pintype "passive"))
      (node (ref "R25") (pin "1") (pinfunction "1_1") (pintype "passive"))
    )
    (net (code "47") (name "Net-(IC3B-IN-)") (class "Default")
      (node (ref "IC3") (pin "6") (pinfunction "IN-_6") (pintype "passive"))
      (node (ref "R21") (pin "2") (pinfunction "2_2") (pintype "passive"))
      (node (ref "R22") (pin "1") (pinfunction "1_1") (pintype "passive"))
    )
    (net (code "48") (name "Net-(IC3B-OUT)") (class "Default")
      (node (ref "IC3") (pin "7") (pinfunction "OUT_7") (pintype "passive"))
      (node (ref "R11") (pin "1") (pinfunction "1_1") (pintype "passive"))
      (node (ref "R19") (pin "1") (pinfunction "1_1") (pintype "passive"))
      (node (ref "R22") (pin "2") (pinfunction "2_2") (pintype "passive"))
      (node (ref "R8") (pin "1") (pinfunction "1_1") (pintype "passive"))
    )
    (net (code "49") (name "Net-(L1-Pad2)") (class "Default")
      (node (ref "L1") (pin "2") (pinfunction "2_2") (pintype "passive"))
      (node (ref "R5") (pin "2") (pinfunction "2_2") (pintype "passive"))
    )
    (net (code "50") (name "Net-(Q1-G)") (class "Default")
      (node (ref "Q1") (pin "1") (pinfunction "G_1") (pintype "passive"))
      (node (ref "R8") (pin "2") (pinfunction "2_2") (pintype "passive"))
    )
    (net (code "51") (name "Net-(Q4-G)") (class "Default")
      (node (ref "Q4") (pin "1") (pinfunction "G_1") (pintype "passive"))
      (node (ref "R34") (pin "2") (pinfunction "2_2") (pintype "passive"))
    )
    (net (code "52") (name "Net-(R20-Pad2)") (class "Default")
      (node (ref "R20") (pin "2") (pinfunction "2_2") (pintype "passive"))
      (node (ref "R25") (pin "2") (pinfunction "2_2") (pintype "passive"))
    )
    (net (code "53") (name "unconnected-(IC1-PA5-Pad16)") (class "Default")
      (node (ref "IC1") (pin "16") (pinfunction "PA5_16") (pintype "passive+no_connect"))
    )
    (net (code "54") (name "unconnected-(IC1-PA6-Pad17)") (class "Default")
      (node (ref "IC1") (pin "17") (pinfunction "PA6_17") (pintype "passive+no_connect"))
    )
    (net (code "55") (name "unconnected-(IC1-PA7-Pad18)") (class "Default")
      (node (ref "IC1") (pin "18") (pinfunction "PA7_18") (pintype "passive+no_connect"))
    )
    (net (code "56") (name "unconnected-(IC1-PA8-Pad28)") (class "Default")
      (node (ref "IC1") (pin "28") (pinfunction "PA8_28") (pintype "passive+no_connect"))
    )
    (net (code "57") (name "unconnected-(IC1-PA11_[PA9]-Pad33)") (class "Default")
      (node (ref "IC1") (pin "33") (pinfunction "PA11_[PA9]_33") (pintype "passive+no_connect"))
    )
    (net (code "58") (name "unconnected-(IC1-PA12_[PA10]-Pad34)") (class "Default")
      (node (ref "IC1") (pin "34") (pinfunction "PA12_[PA10]_34") (pintype "passive+no_connect"))
    )
    (net (code "59") (name "unconnected-(IC1-PA15-Pad37)") (class "Default")
      (node (ref "IC1") (pin "37") (pinfunction "PA15_37") (pintype "passive+no_connect"))
    )
    (net (code "60") (name "unconnected-(IC1-PB1-Pad20)") (class "Default")
      (node (ref "IC1") (pin "20") (pinfunction "PB1_20") (pintype "passive+no_connect"))
    )
    (net (code "61") (name "unconnected-(IC1-PB8-Pad47)") (class "Default")
      (node (ref "IC1") (pin "47") (pinfunction "PB8_47") (pintype "power_in+no_connect"))
    )
    (net (code "62") (name "unconnected-(IC1-PB9-Pad48)") (class "Default")
      (node (ref "IC1") (pin "48") (pinfunction "PB9_48") (pintype "power_in+no_connect"))
    )
    (net (code "63") (name "unconnected-(IC1-PB10-Pad22)") (class "Default")
      (node (ref "IC1") (pin "22") (pinfunction "PB10_22") (pintype "passive+no_connect"))
    )
    (net (code "64") (name "unconnected-(IC1-PB11-Pad23)") (class "Default")
      (node (ref "IC1") (pin "23") (pinfunction "PB11_23") (pintype "power_in+no_connect"))
    )
    (net (code "65") (name "unconnected-(IC1-PB12-Pad24)") (class "Default")
      (node (ref "IC1") (pin "24") (pinfunction "PB12_24") (pintype "power_in+no_connect"))
    )
    (net (code "66") (name "unconnected-(IC1-PB13-Pad25)") (class "Default")
      (node (ref "IC1") (pin "25") (pinfunction "PB13_25") (pintype "passive+no_connect"))
    )
    (net (code "67") (name "unconnected-(IC1-PB14-Pad26)") (class "Default")
      (node (ref "IC1") (pin "26") (pinfunction "PB14_26") (pintype "passive+no_connect"))
    )
    (net (code "68") (name "unconnected-(IC1-PB15-Pad27)") (class "Default")
      (node (ref "IC1") (pin "27") (pinfunction "PB15_27") (pintype "passive+no_connect"))
    )
    (net (code "69") (name "unconnected-(IC1-PC6-Pad30)") (class "Default")
      (node (ref "IC1") (pin "30") (pinfunction "PC6_30") (pintype "passive+no_connect"))
    )
    (net (code "70") (name "unconnected-(IC1-PC7-Pad31)") (class "Default")
      (node (ref "IC1") (pin "31") (pinfunction "PC7_31") (pintype "passive+no_connect"))
    )
    (net (code "71") (name "unconnected-(IC1-PC13-Pad1)") (class "Default")
      (node (ref "IC1") (pin "1") (pinfunction "PC13_1") (pintype "power_in+no_connect"))
    )
    (net (code "72") (name "unconnected-(IC1-PC14-OSC32_IN-Pad2)") (class "Default")
      (node (ref "IC1") (pin "2") (pinfunction "PC14-OSC32_IN_2") (pintype "passive+no_connect"))
    )
    (net (code "73") (name "unconnected-(IC1-PC15-OSC32_OUT-Pad3)") (class "Default")
      (node (ref "IC1") (pin "3") (pinfunction "PC15-OSC32_OUT_3") (pintype "passive+no_connect"))
    )
    (net (code "74") (name "unconnected-(IC3A-IN+-Pad3)") (class "Default")
      (node (ref "IC3") (pin "3") (pinfunction "IN+_3") (pintype "passive+no_connect"))
    )
    (net (code "75") (name "unconnected-(IC3A-IN--Pad2)") (class "Default")
      (node (ref "IC3") (pin "2") (pinfunction "IN-_2") (pintype "passive+no_connect"))
    )
    (net (code "76") (name "unconnected-(IC3A-OUT-Pad1)") (class "Default")
      (node (ref "IC3") (pin "1") (pinfunction "OUT_1") (pintype "passive+no_connect"))
    )
  )
)
